# samd1.net
KiCad netlist of a schematic drawn in EAGLE
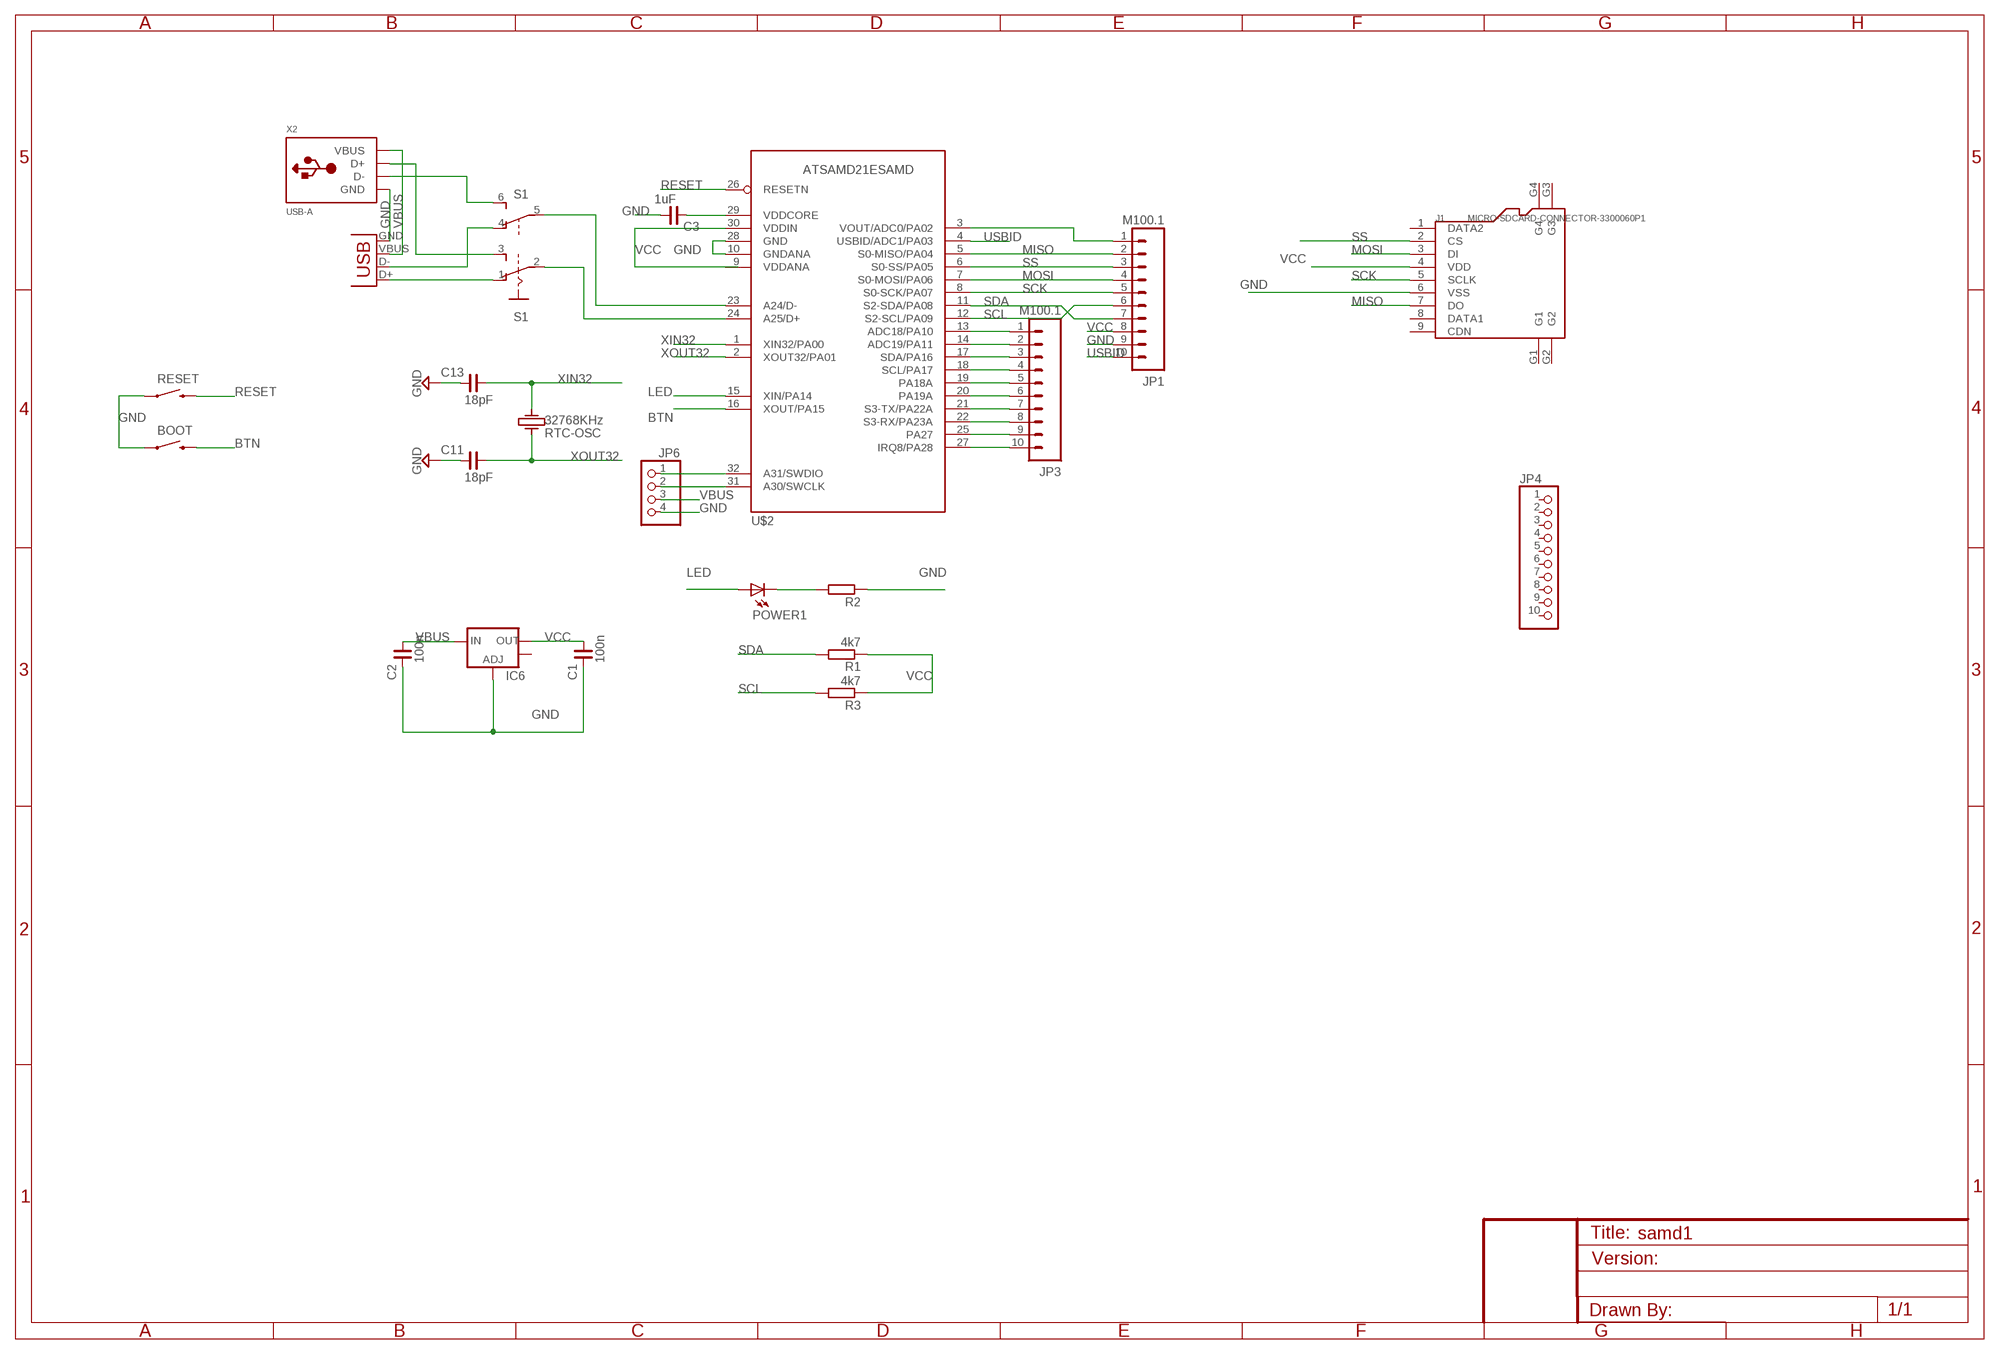
[diagram p0: schematic, sheet 1]

(export (version "E")
  (design (tool "Eeschema 10.0.6"))
  (components
    (comp (ref "BOOT")
      (value "SWITCH-MOMENTARY-2-SMD-1101NE")
      (footprint "eagle-import:TACTILE-SWITCH-1101NE")
      (libsource (lib "eagle-import") (part "SWITCH-MOMENTARY-2-SMD-1101NE"))
    )
    (comp (ref "C1")
      (value "100n")
      (footprint "eagle-import:C0603")
      (libsource (lib "eagle-import") (part "C_0603"))
    )
    (comp (ref "C2")
      (value "100n")
      (footprint "eagle-import:C0603")
      (libsource (lib "eagle-import") (part "C_0603"))
    )
    (comp (ref "C3")
      (value "1uF")
      (footprint "eagle-import:C0603")
      (libsource (lib "eagle-import") (part "C_0603"))
    )
    (comp (ref "C11")
      (value "18pF")
      (footprint "eagle-import:C0603")
      (libsource (lib "eagle-import") (part "C_0603"))
    )
    (comp (ref "C13")
      (value "18pF")
      (footprint "eagle-import:C0603")
      (libsource (lib "eagle-import") (part "C_0603"))
    )
    (comp (ref "IC6")
      (value "V_REG_LM1117SOT223")
      (footprint "eagle-import:SOT223")
      (libsource (lib "eagle-import") (part "V_REG_LM1117SOT223"))
    )
    (comp (ref "J1")
      (value "MICRO-SDCARD-CONNECTOR-3300060P1")
      (footprint "eagle-import:9P-SMD-W-RING")
      (libsource (lib "eagle-import") (part "MICRO-SDCARD-CONNECTOR-3300060P1"))
    )
    (comp (ref "JP1")
      (value "M100.1")
      (footprint "eagle-import:1X10")
      (libsource (lib "eagle-import") (part "M100.1"))
    )
    (comp (ref "JP3")
      (value "M100.1")
      (footprint "eagle-import:1X10")
      (libsource (lib "eagle-import") (part "M100.1"))
    )
    (comp (ref "JP4")
      (value "PINHD-1X10")
      (footprint "eagle-import:1X10")
      (libsource (lib "eagle-import") (part "PINHD-1X10"))
    )
    (comp (ref "JP6")
      (value "PINHD-1X4/90")
      (footprint "eagle-import:1X04_90")
      (libsource (lib "eagle-import") (part "PINHD-1X4/90"))
    )
    (comp (ref "POWER1")
      (value "Power")
      (footprint "eagle-import:LED-0603")
      (libsource (lib "eagle-import") (part "LED0603"))
    )
    (comp (ref "R1")
      (value "4k7")
      (footprint "eagle-import:R0603")
      (libsource (lib "eagle-import") (part "R-EU_R0603"))
    )
    (comp (ref "R2")
      (value "R-EU_R0603")
      (footprint "eagle-import:R0603")
      (libsource (lib "eagle-import") (part "R-EU_R0603"))
    )
    (comp (ref "R3")
      (value "4k7")
      (footprint "eagle-import:R0603")
      (libsource (lib "eagle-import") (part "R-EU_R0603"))
    )
    (comp (ref "RESET")
      (value "SWITCH-MOMENTARY-2-SMD-1101NE")
      (footprint "eagle-import:TACTILE-SWITCH-1101NE")
      (libsource (lib "eagle-import") (part "SWITCH-MOMENTARY-2-SMD-1101NE"))
    )
    (comp (ref "RTC-OSC")
      (value "32768KHz")
      (footprint "eagle-import:KX-327LT")
      (libsource (lib "eagle-import") (part "CRYSTALL"))
    )
    (comp (ref "S1")
      (value "A68-A31")
      (footprint "eagle-import:A68-A31")
      (libsource (lib "eagle-import") (part "A68-A31"))
    )
    (comp (ref "U$2")
      (value "ATSAMD21ESAMD")
      (footprint "eagle-import:TQFP32-08")
      (libsource (lib "eagle-import") (part "ATSAMD21ESAMD"))
    )
    (comp (ref "X2")
      (value "USB-A")
      (footprint "eagle-import:MOLEX_480371000")
      (libsource (lib "eagle-import") (part "USB-A"))
    )
    (comp (ref "X3")
      (value "USB_")
      (footprint "eagle-import:USB-A-S-SILK-FEMALE")
      (libsource (lib "eagle-import") (part "USB_"))
    )
  )
  (nets
    (net (code "1") (name "/BTN") (class "Default")
      (node (ref "BOOT") (pin "P$2") (pinfunction "2_P$2") (pintype "passive"))
      (node (ref "U$2") (pin "16") (pinfunction "XOUT/PA15_16") (pintype "bidirectional"))
    )
    (net (code "2") (name "/LED") (class "Default")
      (node (ref "POWER1") (pin "A") (pinfunction "A_A") (pintype "passive"))
      (node (ref "U$2") (pin "15") (pinfunction "XIN/PA14_15") (pintype "bidirectional"))
    )
    (net (code "3") (name "/MISO") (class "Default")
      (node (ref "J1") (pin "7") (pinfunction "DO_7") (pintype "output"))
      (node (ref "JP1") (pin "2") (pinfunction "2_2") (pintype "passive"))
      (node (ref "U$2") (pin "5") (pinfunction "S0-MISO/PA04_5") (pintype "bidirectional"))
    )
    (net (code "4") (name "/MOSI") (class "Default")
      (node (ref "J1") (pin "3") (pinfunction "DI_3") (pintype "output"))
      (node (ref "JP1") (pin "4") (pinfunction "4_4") (pintype "passive"))
      (node (ref "U$2") (pin "7") (pinfunction "S0-MOSI/PA06_7") (pintype "bidirectional"))
    )
    (net (code "5") (name "/RESET") (class "Default")
      (node (ref "RESET") (pin "P$2") (pinfunction "2_P$2") (pintype "passive"))
      (node (ref "U$2") (pin "26") (pinfunction "RESETN_26") (pintype "bidirectional"))
    )
    (net (code "6") (name "/SCK") (class "Default")
      (node (ref "J1") (pin "5") (pinfunction "SCLK_5") (pintype "output"))
      (node (ref "JP1") (pin "5") (pinfunction "5_5") (pintype "passive"))
      (node (ref "U$2") (pin "8") (pinfunction "S0-SCK/PA07_8") (pintype "bidirectional"))
    )
    (net (code "7") (name "/SCL") (class "Default")
      (node (ref "JP1") (pin "6") (pinfunction "6_6") (pintype "passive"))
      (node (ref "R3") (pin "2") (pinfunction "2_2") (pintype "passive"))
      (node (ref "U$2") (pin "12") (pinfunction "S2-SCL/PA09_12") (pintype "bidirectional"))
    )
    (net (code "8") (name "/SDA") (class "Default")
      (node (ref "JP1") (pin "7") (pinfunction "7_7") (pintype "passive"))
      (node (ref "R1") (pin "2") (pinfunction "2_2") (pintype "passive"))
      (node (ref "U$2") (pin "11") (pinfunction "S2-SDA/PA08_11") (pintype "bidirectional"))
    )
    (net (code "9") (name "/SS") (class "Default")
      (node (ref "J1") (pin "2") (pinfunction "CS_2") (pintype "output"))
      (node (ref "JP1") (pin "3") (pinfunction "3_3") (pintype "passive"))
      (node (ref "U$2") (pin "6") (pinfunction "S0-SS/PA05_6") (pintype "bidirectional"))
    )
    (net (code "10") (name "/USBID") (class "Default")
      (node (ref "JP1") (pin "10") (pinfunction "10_10") (pintype "passive"))
      (node (ref "U$2") (pin "4") (pinfunction "USBID/ADC1/PA03_4") (pintype "bidirectional"))
    )
    (net (code "11") (name "/VBUS") (class "Default")
      (node (ref "C2") (pin "1") (pinfunction "1_1") (pintype "passive"))
      (node (ref "IC6") (pin "3") (pinfunction "IN_3") (pintype "input"))
      (node (ref "JP6") (pin "3") (pinfunction "3_3") (pintype "passive"))
      (node (ref "X2") (pin "1") (pinfunction "VBUS_1") (pintype "power_in"))
      (node (ref "X3") (pin "VBUS") (pinfunction "VBUS_VBUS") (pintype "bidirectional"))
    )
    (net (code "12") (name "/VCC") (class "Default")
      (node (ref "C1") (pin "1") (pinfunction "1_1") (pintype "passive"))
      (node (ref "IC6") (pin "2") (pinfunction "OUT_2") (pintype "output"))
      (node (ref "J1") (pin "4") (pinfunction "VDD_4") (pintype "output"))
      (node (ref "JP1") (pin "8") (pinfunction "8_8") (pintype "passive"))
      (node (ref "R1") (pin "1") (pinfunction "1_1") (pintype "passive"))
      (node (ref "R3") (pin "1") (pinfunction "1_1") (pintype "passive"))
      (node (ref "U$2") (pin "30") (pinfunction "VDDIN_30") (pintype "bidirectional"))
    )
    (net (code "13") (name "/XIN32") (class "Default")
      (node (ref "C13") (pin "1") (pinfunction "1_1") (pintype "passive"))
      (node (ref "RTC-OSC") (pin "1") (pinfunction "P$1_1") (pintype "bidirectional"))
      (node (ref "U$2") (pin "1") (pinfunction "XIN32/PA00_1") (pintype "bidirectional"))
    )
    (net (code "14") (name "/XOUT32") (class "Default")
      (node (ref "C11") (pin "1") (pinfunction "1_1") (pintype "passive"))
      (node (ref "RTC-OSC") (pin "4") (pinfunction "P$2_4") (pintype "bidirectional"))
      (node (ref "U$2") (pin "2") (pinfunction "XOUT32/PA01_2") (pintype "bidirectional"))
    )
    (net (code "15") (name "GND") (class "Default")
      (node (ref "BOOT") (pin "P$1") (pinfunction "1_P$1") (pintype "passive"))
      (node (ref "C1") (pin "2") (pinfunction "2_2") (pintype "passive"))
      (node (ref "C11") (pin "2") (pinfunction "2_2") (pintype "passive"))
      (node (ref "C13") (pin "2") (pinfunction "2_2") (pintype "passive"))
      (node (ref "C2") (pin "2") (pinfunction "2_2") (pintype "passive"))
      (node (ref "C3") (pin "1") (pinfunction "1_1") (pintype "passive"))
      (node (ref "IC6") (pin "1") (pinfunction "ADJ_1") (pintype "input"))
      (node (ref "J1") (pin "6") (pinfunction "VSS_6") (pintype "output"))
      (node (ref "JP1") (pin "9") (pinfunction "9_9") (pintype "passive"))
      (node (ref "JP6") (pin "4") (pinfunction "4_4") (pintype "passive"))
      (node (ref "R2") (pin "1") (pinfunction "1_1") (pintype "passive"))
      (node (ref "RESET") (pin "P$1") (pinfunction "1_P$1") (pintype "passive"))
      (node (ref "U$2") (pin "10") (pinfunction "GNDANA_10") (pintype "bidirectional"))
      (node (ref "U$2") (pin "28") (pinfunction "GND_28") (pintype "bidirectional"))
      (node (ref "X2") (pin "4") (pinfunction "GND_4") (pintype "power_in"))
      (node (ref "X3") (pin "GND") (pinfunction "GND_GND") (pintype "bidirectional"))
    )
    (net (code "16") (name "Net-(POWER1-PadC)") (class "Default")
      (node (ref "POWER1") (pin "C") (pinfunction "C_C") (pintype "passive"))
      (node (ref "R2") (pin "2") (pinfunction "2_2") (pintype "passive"))
    )
    (net (code "17") (name "Net-(S1A-O)") (class "Default")
      (node (ref "S1") (pin "1") (pinfunction "O_1") (pintype "passive"))
      (node (ref "X3") (pin "D+") (pinfunction "D+_D+") (pintype "bidirectional"))
    )
    (net (code "18") (name "Net-(S1A-P)") (class "Default")
      (node (ref "S1") (pin "2") (pinfunction "P_2") (pintype "passive"))
      (node (ref "U$2") (pin "24") (pinfunction "A25/D+_24") (pintype "bidirectional"))
    )
    (net (code "19") (name "Net-(S1A-S)") (class "Default")
      (node (ref "S1") (pin "3") (pinfunction "S_3") (pintype "passive"))
      (node (ref "X2") (pin "3") (pinfunction "D+_3") (pintype "bidirectional"))
    )
    (net (code "20") (name "Net-(S1B-O)") (class "Default")
      (node (ref "S1") (pin "4") (pinfunction "O_4") (pintype "passive"))
      (node (ref "X3") (pin "D-") (pinfunction "D-_D-") (pintype "bidirectional"))
    )
    (net (code "21") (name "Net-(S1B-P)") (class "Default")
      (node (ref "S1") (pin "5") (pinfunction "P_5") (pintype "passive"))
      (node (ref "U$2") (pin "23") (pinfunction "A24/D-_23") (pintype "bidirectional"))
    )
    (net (code "22") (name "Net-(S1B-S)") (class "Default")
      (node (ref "S1") (pin "6") (pinfunction "S_6") (pintype "passive"))
      (node (ref "X2") (pin "2") (pinfunction "D-_2") (pintype "bidirectional"))
    )
    (net (code "23") (name "Net-(U$2-A30{slash}SWCLK)") (class "Default")
      (node (ref "JP6") (pin "2") (pinfunction "2_2") (pintype "passive"))
      (node (ref "U$2") (pin "31") (pinfunction "A30/SWCLK_31") (pintype "bidirectional"))
    )
    (net (code "24") (name "Net-(U$2-A31{slash}SWDIO)") (class "Default")
      (node (ref "JP6") (pin "1") (pinfunction "1_1") (pintype "passive"))
      (node (ref "U$2") (pin "32") (pinfunction "A31/SWDIO_32") (pintype "bidirectional"))
    )
    (net (code "25") (name "Net-(U$2-ADC18{slash}PA10)") (class "Default")
      (node (ref "JP3") (pin "1") (pinfunction "1_1") (pintype "passive"))
      (node (ref "U$2") (pin "13") (pinfunction "ADC18/PA10_13") (pintype "bidirectional"))
    )
    (net (code "26") (name "Net-(U$2-ADC19{slash}PA11)") (class "Default")
      (node (ref "JP3") (pin "2") (pinfunction "2_2") (pintype "passive"))
      (node (ref "U$2") (pin "14") (pinfunction "ADC19/PA11_14") (pintype "bidirectional"))
    )
    (net (code "27") (name "Net-(U$2-IRQ8{slash}PA28)") (class "Default")
      (node (ref "JP3") (pin "10") (pinfunction "10_10") (pintype "passive"))
      (node (ref "U$2") (pin "27") (pinfunction "IRQ8/PA28_27") (pintype "bidirectional"))
    )
    (net (code "28") (name "Net-(U$2-PA18A)") (class "Default")
      (node (ref "JP3") (pin "5") (pinfunction "5_5") (pintype "passive"))
      (node (ref "U$2") (pin "19") (pinfunction "PA18A_19") (pintype "bidirectional"))
    )
    (net (code "29") (name "Net-(U$2-PA19A)") (class "Default")
      (node (ref "JP3") (pin "6") (pinfunction "6_6") (pintype "passive"))
      (node (ref "U$2") (pin "20") (pinfunction "PA19A_20") (pintype "bidirectional"))
    )
    (net (code "30") (name "Net-(U$2-PA27)") (class "Default")
      (node (ref "JP3") (pin "9") (pinfunction "9_9") (pintype "passive"))
      (node (ref "U$2") (pin "25") (pinfunction "PA27_25") (pintype "bidirectional"))
    )
    (net (code "31") (name "Net-(U$2-S3-RX{slash}PA23A)") (class "Default")
      (node (ref "JP3") (pin "8") (pinfunction "8_8") (pintype "passive"))
      (node (ref "U$2") (pin "22") (pinfunction "S3-RX/PA23A_22") (pintype "bidirectional"))
    )
    (net (code "32") (name "Net-(U$2-S3-TX{slash}PA22A)") (class "Default")
      (node (ref "JP3") (pin "7") (pinfunction "7_7") (pintype "passive"))
      (node (ref "U$2") (pin "21") (pinfunction "S3-TX/PA22A_21") (pintype "bidirectional"))
    )
    (net (code "33") (name "Net-(U$2-SCL{slash}PA17)") (class "Default")
      (node (ref "JP3") (pin "4") (pinfunction "4_4") (pintype "passive"))
      (node (ref "U$2") (pin "18") (pinfunction "SCL/PA17_18") (pintype "bidirectional"))
    )
    (net (code "34") (name "Net-(U$2-SDA{slash}PA16)") (class "Default")
      (node (ref "JP3") (pin "3") (pinfunction "3_3") (pintype "passive"))
      (node (ref "U$2") (pin "17") (pinfunction "SDA/PA16_17") (pintype "bidirectional"))
    )
    (net (code "35") (name "Net-(U$2-VDDCORE)") (class "Default")
      (node (ref "C3") (pin "2") (pinfunction "2_2") (pintype "passive"))
      (node (ref "U$2") (pin "29") (pinfunction "VDDCORE_29") (pintype "bidirectional"))
    )
    (net (code "36") (name "Net-(U$2-VOUT{slash}ADC0{slash}PA02)") (class "Default")
      (node (ref "JP1") (pin "1") (pinfunction "1_1") (pintype "passive"))
      (node (ref "U$2") (pin "3") (pinfunction "VOUT/ADC0/PA02_3") (pintype "bidirectional"))
    )
    (net (code "37") (name "unconnected-(IC6-OUT-Pad4)") (class "Default")
      (node (ref "IC6") (pin "4") (pinfunction "OUT_4") (pintype "output"))
    )
    (net (code "38") (name "unconnected-(J1-CDN-Pad9)") (class "Default")
      (node (ref "J1") (pin "9") (pinfunction "CDN_9") (pintype "output"))
    )
    (net (code "39") (name "unconnected-(J1-DATA1-Pad8)") (class "Default")
      (node (ref "J1") (pin "8") (pinfunction "DATA1_8") (pintype "output"))
    )
    (net (code "40") (name "unconnected-(J1-DATA2-Pad1)") (class "Default")
      (node (ref "J1") (pin "1") (pinfunction "DATA2_1") (pintype "output"))
    )
    (net (code "41") (name "unconnected-(J1-PadG1)") (class "Default")
      (node (ref "J1") (pin "G1") (pinfunction "G1_G1") (pintype "output"))
    )
    (net (code "42") (name "unconnected-(J1-PadG2)") (class "Default")
      (node (ref "J1") (pin "G2") (pinfunction "G2_G2") (pintype "output"))
    )
    (net (code "43") (name "unconnected-(J1-PadG3)") (class "Default")
      (node (ref "J1") (pin "G3") (pinfunction "G3_G3") (pintype "output"))
    )
    (net (code "44") (name "unconnected-(J1-PadG4)") (class "Default")
      (node (ref "J1") (pin "G4") (pinfunction "G4_G4") (pintype "output"))
    )
    (net (code "45") (name "unconnected-(JP4-Pad1)") (class "Default")
      (node (ref "JP4") (pin "1") (pinfunction "1_1") (pintype "passive"))
    )
    (net (code "46") (name "unconnected-(JP4-Pad2)") (class "Default")
      (node (ref "JP4") (pin "2") (pinfunction "2_2") (pintype "passive"))
    )
    (net (code "47") (name "unconnected-(JP4-Pad3)") (class "Default")
      (node (ref "JP4") (pin "3") (pinfunction "3_3") (pintype "passive"))
    )
    (net (code "48") (name "unconnected-(JP4-Pad4)") (class "Default")
      (node (ref "JP4") (pin "4") (pinfunction "4_4") (pintype "passive"))
    )
    (net (code "49") (name "unconnected-(JP4-Pad5)") (class "Default")
      (node (ref "JP4") (pin "5") (pinfunction "5_5") (pintype "passive"))
    )
    (net (code "50") (name "unconnected-(JP4-Pad6)") (class "Default")
      (node (ref "JP4") (pin "6") (pinfunction "6_6") (pintype "passive"))
    )
    (net (code "51") (name "unconnected-(JP4-Pad7)") (class "Default")
      (node (ref "JP4") (pin "7") (pinfunction "7_7") (pintype "passive"))
    )
    (net (code "52") (name "unconnected-(JP4-Pad8)") (class "Default")
      (node (ref "JP4") (pin "8") (pinfunction "8_8") (pintype "passive"))
    )
    (net (code "53") (name "unconnected-(JP4-Pad9)") (class "Default")
      (node (ref "JP4") (pin "9") (pinfunction "9_9") (pintype "passive"))
    )
    (net (code "54") (name "unconnected-(JP4-Pad10)") (class "Default")
      (node (ref "JP4") (pin "10") (pinfunction "10_10") (pintype "passive"))
    )
    (net (code "55") (name "unconnected-(U$2-VDDANA-Pad9)") (class "Default")
      (node (ref "U$2") (pin "9") (pinfunction "VDDANA_9") (pintype "bidirectional"))
    )
  )
)
